# 12V_Converter.net
KiCad netlist of a schematic drawn in Altium Designer
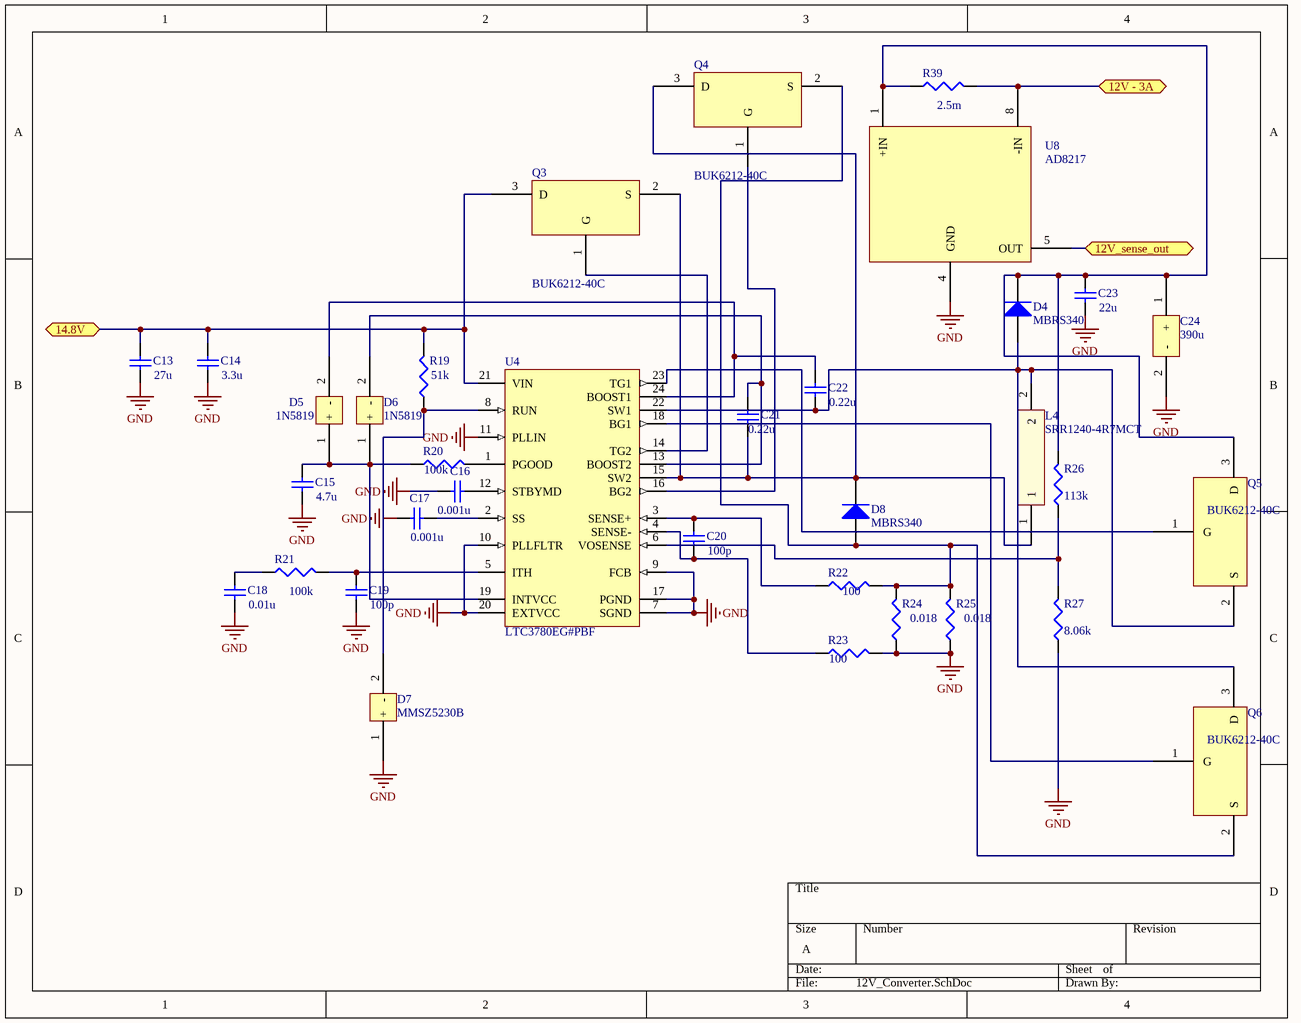
[diagram p0: 12V_Converter.SchDoc]

(export (version "E")
  (design (tool "Eeschema 10.0.6"))
  (components
    (comp (ref "C13")
      (value "27u")
      (footprint "C1206")
      (description "Capacitor (Semiconductor SIM Model)")
      (fields (field (name "Comment") "Cap Semi") (field (name "PUBLISHER") "Altium Limited"))
      (libsource (lib "Miscellaneous Devices") (part "Cap Semi"))
    )
    (comp (ref "C14")
      (value "3.3u")
      (footprint "C1206")
      (description "Capacitor (Semiconductor SIM Model)")
      (fields (field (name "Comment") "Cap Semi") (field (name "PUBLISHER") "Altium Limited"))
      (libsource (lib "Miscellaneous Devices") (part "Cap Semi"))
    )
    (comp (ref "C15")
      (value "4.7u")
      (footprint "C1206")
      (description "Capacitor (Semiconductor SIM Model)")
      (fields (field (name "Comment") "Cap Semi") (field (name "PUBLISHER") "Altium Limited"))
      (libsource (lib "Miscellaneous Devices") (part "Cap Semi"))
    )
    (comp (ref "C16")
      (value "0.001u")
      (footprint "C1206")
      (description "Capacitor (Semiconductor SIM Model)")
      (fields (field (name "Comment") "Cap Semi") (field (name "PUBLISHER") "Altium Limited"))
      (libsource (lib "Miscellaneous Devices") (part "Cap Semi"))
    )
    (comp (ref "C17")
      (value "0.001u")
      (footprint "C1206")
      (description "Capacitor (Semiconductor SIM Model)")
      (fields (field (name "Comment") "Cap Semi") (field (name "PUBLISHER") "Altium Limited"))
      (libsource (lib "Miscellaneous Devices") (part "Cap Semi"))
    )
    (comp (ref "C18")
      (value "0.01u")
      (footprint "C1206")
      (description "Capacitor (Semiconductor SIM Model)")
      (fields (field (name "Comment") "Cap Semi") (field (name "PUBLISHER") "Altium Limited"))
      (libsource (lib "Miscellaneous Devices") (part "Cap Semi"))
    )
    (comp (ref "C19")
      (value "100p")
      (footprint "C1206")
      (description "Capacitor (Semiconductor SIM Model)")
      (fields (field (name "Comment") "Cap Semi") (field (name "PUBLISHER") "Altium Limited"))
      (libsource (lib "Miscellaneous Devices") (part "Cap Semi"))
    )
    (comp (ref "C20")
      (value "100p")
      (footprint "C1206")
      (description "Capacitor (Semiconductor SIM Model)")
      (fields (field (name "Comment") "Cap Semi") (field (name "PUBLISHER") "Altium Limited"))
      (libsource (lib "Miscellaneous Devices") (part "Cap Semi"))
    )
    (comp (ref "C21")
      (value "0.22u")
      (footprint "C1206")
      (description "Capacitor (Semiconductor SIM Model)")
      (fields (field (name "Comment") "Cap Semi") (field (name "PUBLISHER") "Altium Limited"))
      (libsource (lib "Miscellaneous Devices") (part "Cap Semi"))
    )
    (comp (ref "C22")
      (value "0.22u")
      (footprint "C1206")
      (description "Capacitor (Semiconductor SIM Model)")
      (fields (field (name "Comment") "Cap Semi") (field (name "PUBLISHER") "Altium Limited"))
      (libsource (lib "Miscellaneous Devices") (part "Cap Semi"))
    )
    (comp (ref "C23")
      (value "22u")
      (footprint "C1206")
      (description "Capacitor (Semiconductor SIM Model)")
      (fields (field (name "Comment") "Cap Semi") (field (name "PUBLISHER") "Altium Limited"))
      (libsource (lib "Miscellaneous Devices") (part "Cap Semi"))
    )
    (comp (ref "C24") (value "390u") (footprint "Alum_Cap") (libsource (lib "AluminumCap") (part "Alum_Cap")))
    (comp (ref "D4")
      (value "MBRS340")
      (footprint "SMC")
      (description "Default Diode")
      (fields (field (name "PUBLISHER") "Altium Limited"))
      (libsource (lib "Miscellaneous Devices") (part "Diode"))
    )
    (comp (ref "D5")
      (value "1N5819")
      (footprint "SOD-123")
      (libsource (lib "Diode (1N5819)") (part "Component_1"))
    )
    (comp (ref "D6")
      (value "1N5819")
      (footprint "SOD-123")
      (libsource (lib "Diode (1N5819)") (part "Component_1"))
    )
    (comp (ref "D7")
      (value "MMSZ5230B")
      (footprint "SOD-123")
      (libsource (lib "Diode (1N5819)") (part "Component_1"))
    )
    (comp (ref "D8")
      (value "MBRS340")
      (footprint "SMC")
      (description "Default Diode")
      (fields (field (name "PUBLISHER") "Altium Limited"))
      (libsource (lib "Miscellaneous Devices") (part "Diode"))
    )
    (comp (ref "L4")
      (value "SRR1240-4R7MCT")
      (footprint "INDP125125X45N")
      (libsource (lib "SRR1240-4R7MCT") (part "SRR1240-4R7MCT"))
    )
    (comp (ref "Q3")
      (value "BUK6212-40C")
      (footprint "SOT457P1000X238-3N")
      (libsource (lib "BUK6212-40C") (part "Component_1"))
    )
    (comp (ref "Q4")
      (value "BUK6212-40C")
      (footprint "SOT457P1000X238-3N")
      (libsource (lib "BUK6212-40C") (part "Component_1"))
    )
    (comp (ref "Q5")
      (value "BUK6212-40C")
      (footprint "SOT457P1000X238-3N")
      (libsource (lib "") (part "Component_1_1"))
    )
    (comp (ref "Q6")
      (value "BUK6212-40C")
      (footprint "SOT457P1000X238-3N")
      (libsource (lib "") (part "Component_1_1"))
    )
    (comp (ref "R19")
      (value "51k")
      (footprint "J1-0603")
      (description "Resistor")
      (fields (field (name "Comment") "Res3") (field (name "PUBLISHER") "Altium Limited"))
      (libsource (lib "Miscellaneous Devices") (part "Res3"))
    )
    (comp (ref "R20")
      (value "100k")
      (footprint "J1-0603")
      (description "Resistor")
      (fields (field (name "Comment") "Res3") (field (name "PUBLISHER") "Altium Limited"))
      (libsource (lib "Miscellaneous Devices") (part "Res3"))
    )
    (comp (ref "R21")
      (value "100k")
      (footprint "J1-0603")
      (description "Resistor")
      (fields (field (name "Comment") "Res3") (field (name "PUBLISHER") "Altium Limited"))
      (libsource (lib "Miscellaneous Devices") (part "Res3"))
    )
    (comp (ref "R22")
      (value "100")
      (footprint "J1-0603")
      (description "Resistor")
      (fields (field (name "Comment") "Res3") (field (name "PUBLISHER") "Altium Limited"))
      (libsource (lib "Miscellaneous Devices") (part "Res3"))
    )
    (comp (ref "R23")
      (value "100")
      (footprint "J1-0603")
      (description "Resistor")
      (fields (field (name "Comment") "Res3") (field (name "PUBLISHER") "Altium Limited"))
      (libsource (lib "Miscellaneous Devices") (part "Res3"))
    )
    (comp (ref "R24")
      (value "0.018")
      (footprint "J1-0603")
      (description "Resistor")
      (fields (field (name "Comment") "Res3") (field (name "PUBLISHER") "Altium Limited"))
      (libsource (lib "Miscellaneous Devices") (part "Res3"))
    )
    (comp (ref "R25")
      (value "0.018")
      (footprint "J1-0603")
      (description "Resistor")
      (fields (field (name "Comment") "Res3") (field (name "PUBLISHER") "Altium Limited"))
      (libsource (lib "Miscellaneous Devices") (part "Res3"))
    )
    (comp (ref "R26")
      (value "113k")
      (footprint "J1-0603")
      (description "Resistor")
      (fields (field (name "Comment") "Res3") (field (name "PUBLISHER") "Altium Limited"))
      (libsource (lib "Miscellaneous Devices") (part "Res3"))
    )
    (comp (ref "R27")
      (value "8.06k")
      (footprint "J1-0603")
      (description "Resistor")
      (fields (field (name "Comment") "Res3") (field (name "PUBLISHER") "Altium Limited"))
      (libsource (lib "Miscellaneous Devices") (part "Res3"))
    )
    (comp (ref "R39")
      (value "2.5m")
      (footprint "J1-0603")
      (description "Resistor")
      (fields (field (name "Comment") "Res3") (field (name "PUBLISHER") "Altium Limited"))
      (libsource (lib "Miscellaneous Devices") (part "Res3"))
    )
    (comp (ref "U4")
      (value "LTC3780EG#PBF")
      (footprint "LT-G-24_N")
      (fields (field (name "MANUFACTURER") "Linear Technology"))
      (libsource (lib "Linear Technology Power Management Switching Regulator LTC1174-LTC3901") (part "LTC3780EG#PBF"))
    )
    (comp (ref "U8")
      (value "AD8217")
      (footprint "TSOP65P490X110-8N")
      (description "Current Shunt Moniter")
      (libsource (lib "AD8217") (part "Component_1"))
    )
  )
  (nets
    (net (code "1") (name "/12V - 3A") (class "Default")
      (node (ref "R39") (pin "2") (pinfunction "2_2") (pintype "passive"))
      (node (ref "U8") (pin "8") (pinfunction "-IN_8") (pintype "passive"))
    )
    (net (code "2") (name "/12V_sense_out") (class "Default")
      (node (ref "U8") (pin "5") (pinfunction "OUT_5") (pintype "passive"))
    )
    (net (code "3") (name "/14.8V") (class "Default")
      (node (ref "C13") (pin "2") (pinfunction "2_2") (pintype "passive"))
      (node (ref "C14") (pin "2") (pinfunction "2_2") (pintype "passive"))
      (node (ref "Q3") (pin "3") (pinfunction "D_3") (pintype "passive"))
      (node (ref "R19") (pin "2") (pinfunction "2_2") (pintype "passive"))
      (node (ref "U4") (pin "21") (pinfunction "VIN_21") (pintype "power_in"))
    )
    (net (code "4") (name "GND") (class "Default")
      (node (ref "C13") (pin "1") (pinfunction "1_1") (pintype "passive"))
      (node (ref "C14") (pin "1") (pinfunction "1_1") (pintype "passive"))
      (node (ref "C15") (pin "1") (pinfunction "1_1") (pintype "passive"))
      (node (ref "C16") (pin "1") (pinfunction "1_1") (pintype "passive"))
      (node (ref "C17") (pin "1") (pinfunction "1_1") (pintype "passive"))
      (node (ref "C18") (pin "1") (pinfunction "1_1") (pintype "passive"))
      (node (ref "C19") (pin "1") (pinfunction "1_1") (pintype "passive"))
      (node (ref "C23") (pin "1") (pinfunction "1_1") (pintype "passive"))
      (node (ref "C24") (pin "2") (pinfunction "-_2") (pintype "passive"))
      (node (ref "D7") (pin "1") (pinfunction "+_1") (pintype "passive"))
      (node (ref "R23") (pin "2") (pinfunction "2_2") (pintype "passive"))
      (node (ref "R24") (pin "1") (pinfunction "1_1") (pintype "passive"))
      (node (ref "R25") (pin "1") (pinfunction "1_1") (pintype "passive"))
      (node (ref "R27") (pin "1") (pinfunction "1_1") (pintype "passive"))
      (node (ref "U4") (pin "10") (pinfunction "PLLFLTR_10") (pintype "input"))
      (node (ref "U4") (pin "11") (pinfunction "PLLIN_11") (pintype "input"))
      (node (ref "U4") (pin "17") (pinfunction "PGND_17") (pintype "power_in"))
      (node (ref "U4") (pin "20") (pinfunction "EXTVCC_20") (pintype "power_in"))
      (node (ref "U4") (pin "7") (pinfunction "SGND_7") (pintype "power_in"))
      (node (ref "U4") (pin "9") (pinfunction "FCB_9") (pintype "input"))
      (node (ref "U8") (pin "4") (pinfunction "GND_4") (pintype "passive"))
    )
    (net (code "5") (name "Net-(C18-Pad2)") (class "Default")
      (node (ref "C18") (pin "2") (pinfunction "2_2") (pintype "passive"))
      (node (ref "R21") (pin "1") (pinfunction "1_1") (pintype "passive"))
    )
    (net (code "6") (name "Net-(C24-+)") (class "Default")
      (node (ref "C23") (pin "2") (pinfunction "2_2") (pintype "passive"))
      (node (ref "C24") (pin "1") (pinfunction "+_1") (pintype "passive"))
      (node (ref "D4") (pin "2") (pinfunction "K_2") (pintype "passive"))
      (node (ref "Q5") (pin "3") (pinfunction "D_3") (pintype "passive"))
      (node (ref "R26") (pin "2") (pinfunction "2_2") (pintype "passive"))
      (node (ref "R39") (pin "1") (pinfunction "1_1") (pintype "passive"))
      (node (ref "U8") (pin "1") (pinfunction "+IN_1") (pintype "passive"))
    )
    (net (code "7") (name "Net-(D4-A)") (class "Default")
      (node (ref "C22") (pin "1") (pinfunction "1_1") (pintype "passive"))
      (node (ref "D4") (pin "1") (pinfunction "A_1") (pintype "passive"))
      (node (ref "L4") (pin "2") (pinfunction "2_2") (pintype "passive"))
      (node (ref "Q5") (pin "2") (pinfunction "S_2") (pintype "passive"))
      (node (ref "Q6") (pin "3") (pinfunction "D_3") (pintype "passive"))
      (node (ref "U4") (pin "22") (pinfunction "SW1_22") (pintype "passive"))
    )
    (net (code "8") (name "Net-(D5-+)") (class "Default")
      (node (ref "C15") (pin "2") (pinfunction "2_2") (pintype "passive"))
      (node (ref "D5") (pin "1") (pinfunction "+_1") (pintype "passive"))
      (node (ref "D6") (pin "1") (pinfunction "+_1") (pintype "passive"))
      (node (ref "R20") (pin "1") (pinfunction "1_1") (pintype "passive"))
      (node (ref "U4") (pin "19") (pinfunction "INTVCC_19") (pintype "power_in"))
    )
    (net (code "9") (name "Net-(D5--)") (class "Default")
      (node (ref "C22") (pin "2") (pinfunction "2_2") (pintype "passive"))
      (node (ref "D5") (pin "2") (pinfunction "-_2") (pintype "passive"))
      (node (ref "U4") (pin "24") (pinfunction "BOOST1_24") (pintype "passive"))
    )
    (net (code "10") (name "Net-(D6--)") (class "Default")
      (node (ref "C21") (pin "2") (pinfunction "2_2") (pintype "passive"))
      (node (ref "D6") (pin "2") (pinfunction "-_2") (pintype "passive"))
      (node (ref "U4") (pin "13") (pinfunction "BOOST2_13") (pintype "passive"))
    )
    (net (code "11") (name "Net-(D7--)") (class "Default")
      (node (ref "D7") (pin "2") (pinfunction "-_2") (pintype "passive"))
      (node (ref "R19") (pin "1") (pinfunction "1_1") (pintype "passive"))
      (node (ref "U4") (pin "8") (pinfunction "RUN_8") (pintype "input"))
    )
    (net (code "12") (name "Net-(D8-A)") (class "Default")
      (node (ref "D8") (pin "1") (pinfunction "A_1") (pintype "passive"))
      (node (ref "Q4") (pin "2") (pinfunction "S_2") (pintype "passive"))
      (node (ref "Q6") (pin "2") (pinfunction "S_2") (pintype "passive"))
      (node (ref "R22") (pin "2") (pinfunction "2_2") (pintype "passive"))
      (node (ref "R24") (pin "2") (pinfunction "2_2") (pintype "passive"))
      (node (ref "R25") (pin "2") (pinfunction "2_2") (pintype "passive"))
    )
    (net (code "13") (name "Net-(D8-K)") (class "Default")
      (node (ref "C21") (pin "1") (pinfunction "1_1") (pintype "passive"))
      (node (ref "D8") (pin "2") (pinfunction "K_2") (pintype "passive"))
      (node (ref "L4") (pin "1") (pinfunction "1_1") (pintype "passive"))
      (node (ref "Q3") (pin "2") (pinfunction "S_2") (pintype "passive"))
      (node (ref "Q4") (pin "3") (pinfunction "D_3") (pintype "passive"))
      (node (ref "U4") (pin "15") (pinfunction "SW2_15") (pintype "passive"))
    )
    (net (code "14") (name "Net-(Q3-G)") (class "Default")
      (node (ref "Q3") (pin "1") (pinfunction "G_1") (pintype "passive"))
      (node (ref "U4") (pin "14") (pinfunction "TG2_14") (pintype "output"))
    )
    (net (code "15") (name "Net-(Q4-G)") (class "Default")
      (node (ref "Q4") (pin "1") (pinfunction "G_1") (pintype "passive"))
      (node (ref "U4") (pin "16") (pinfunction "BG2_16") (pintype "output"))
    )
    (net (code "16") (name "Net-(Q5-G)") (class "Default")
      (node (ref "Q5") (pin "1") (pinfunction "G_1") (pintype "passive"))
      (node (ref "U4") (pin "23") (pinfunction "TG1_23") (pintype "output"))
    )
    (net (code "17") (name "Net-(Q6-G)") (class "Default")
      (node (ref "Q6") (pin "1") (pinfunction "G_1") (pintype "passive"))
      (node (ref "U4") (pin "18") (pinfunction "BG1_18") (pintype "output"))
    )
    (net (code "18") (name "Net-(U4-ITH)") (class "Default")
      (node (ref "C19") (pin "2") (pinfunction "2_2") (pintype "passive"))
      (node (ref "R21") (pin "2") (pinfunction "2_2") (pintype "passive"))
      (node (ref "U4") (pin "5") (pinfunction "ITH_5") (pintype "passive"))
    )
    (net (code "19") (name "Net-(U4-PGOOD)") (class "Default")
      (node (ref "R20") (pin "2") (pinfunction "2_2") (pintype "passive"))
      (node (ref "U4") (pin "1") (pinfunction "PGOOD_1") (pintype "open_collector"))
    )
    (net (code "20") (name "Net-(U4-SENSE+)") (class "Default")
      (node (ref "C20") (pin "2") (pinfunction "2_2") (pintype "passive"))
      (node (ref "R22") (pin "1") (pinfunction "1_1") (pintype "passive"))
      (node (ref "U4") (pin "3") (pinfunction "SENSE+_3") (pintype "input"))
    )
    (net (code "21") (name "Net-(U4-SENSE-)") (class "Default")
      (node (ref "C20") (pin "1") (pinfunction "1_1") (pintype "passive"))
      (node (ref "R23") (pin "1") (pinfunction "1_1") (pintype "passive"))
      (node (ref "U4") (pin "4") (pinfunction "SENSE-_4") (pintype "input"))
    )
    (net (code "22") (name "Net-(U4-SS)") (class "Default")
      (node (ref "C17") (pin "2") (pinfunction "2_2") (pintype "passive"))
      (node (ref "U4") (pin "2") (pinfunction "SS_2") (pintype "input"))
    )
    (net (code "23") (name "Net-(U4-STBYMD)") (class "Default")
      (node (ref "C16") (pin "2") (pinfunction "2_2") (pintype "passive"))
      (node (ref "U4") (pin "12") (pinfunction "STBYMD_12") (pintype "input"))
    )
    (net (code "24") (name "Net-(U4-VOSENSE)") (class "Default")
      (node (ref "R26") (pin "1") (pinfunction "1_1") (pintype "passive"))
      (node (ref "R27") (pin "2") (pinfunction "2_2") (pintype "passive"))
      (node (ref "U4") (pin "6") (pinfunction "VOSENSE_6") (pintype "input"))
    )
  )
)
